# HBridgeInterface.net
KiCad netlist of a schematic drawn in Altium Designer
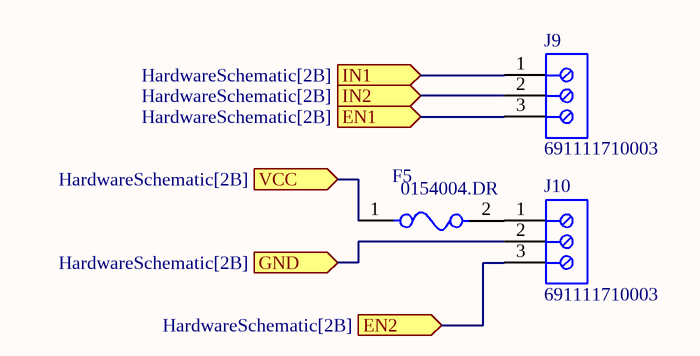
[diagram p0: HBridgeInterface.SchDoc]

(export (version "E")
  (design (tool "Eeschema 10.0.6"))
  (components
    (comp (ref "F5")
      (value "0154004.DR")
      (footprint "FP-0154-MFG")
      (description "FUSE BRD MNT 4A 125VAC/VDC 2SMD")
      (fields
        (field (name "MANUFACTURER") "Littelfuse")
        (field (name "OCTOPART") "https://octopart.com/0154004.dr-littelfuse-565861")
      )
      (libsource (lib "Altium Content Vault") (part "5bcf9b9f640e542cf0359d10258e979"))
    )
    (comp (ref "J9")
      (value "691111710003")
      (footprint "691111710003")
      (fields (field (name "VOLTAGE") "300V"))
      (libsource (lib "Altium Content Vault") (part "TBL - 1R - 03P - Screw"))
    )
    (comp (ref "J10")
      (value "691111710003")
      (footprint "691111710003")
      (fields (field (name "VOLTAGE") "300V"))
      (libsource (lib "Altium Content Vault") (part "TBL - 1R - 03P - Screw"))
    )
  )
  (nets
    (net (code "1") (name "/EN1") (class "Default")
      (node (ref "J9") (pin "3") (pinfunction "3_3") (pintype "passive"))
    )
    (net (code "2") (name "/EN2") (class "Default")
      (node (ref "J10") (pin "3") (pinfunction "3_3") (pintype "passive"))
    )
    (net (code "3") (name "/GND") (class "Default")
      (node (ref "J10") (pin "2") (pinfunction "2_2") (pintype "passive"))
    )
    (net (code "4") (name "/IN1") (class "Default")
      (node (ref "J9") (pin "1") (pinfunction "1_1") (pintype "passive"))
    )
    (net (code "5") (name "/IN2") (class "Default")
      (node (ref "J9") (pin "2") (pinfunction "2_2") (pintype "passive"))
    )
    (net (code "6") (name "/VCC") (class "Default")
      (node (ref "F5") (pin "1") (pinfunction "1_1") (pintype "passive"))
    )
    (net (code "7") (name "Net-(F5-Pad2)") (class "Default")
      (node (ref "F5") (pin "2") (pinfunction "2_2") (pintype "passive"))
      (node (ref "J10") (pin "1") (pinfunction "1_1") (pintype "passive"))
    )
  )
)
